# tvout_terminal.net
KiCad netlist of a schematic drawn in EAGLE
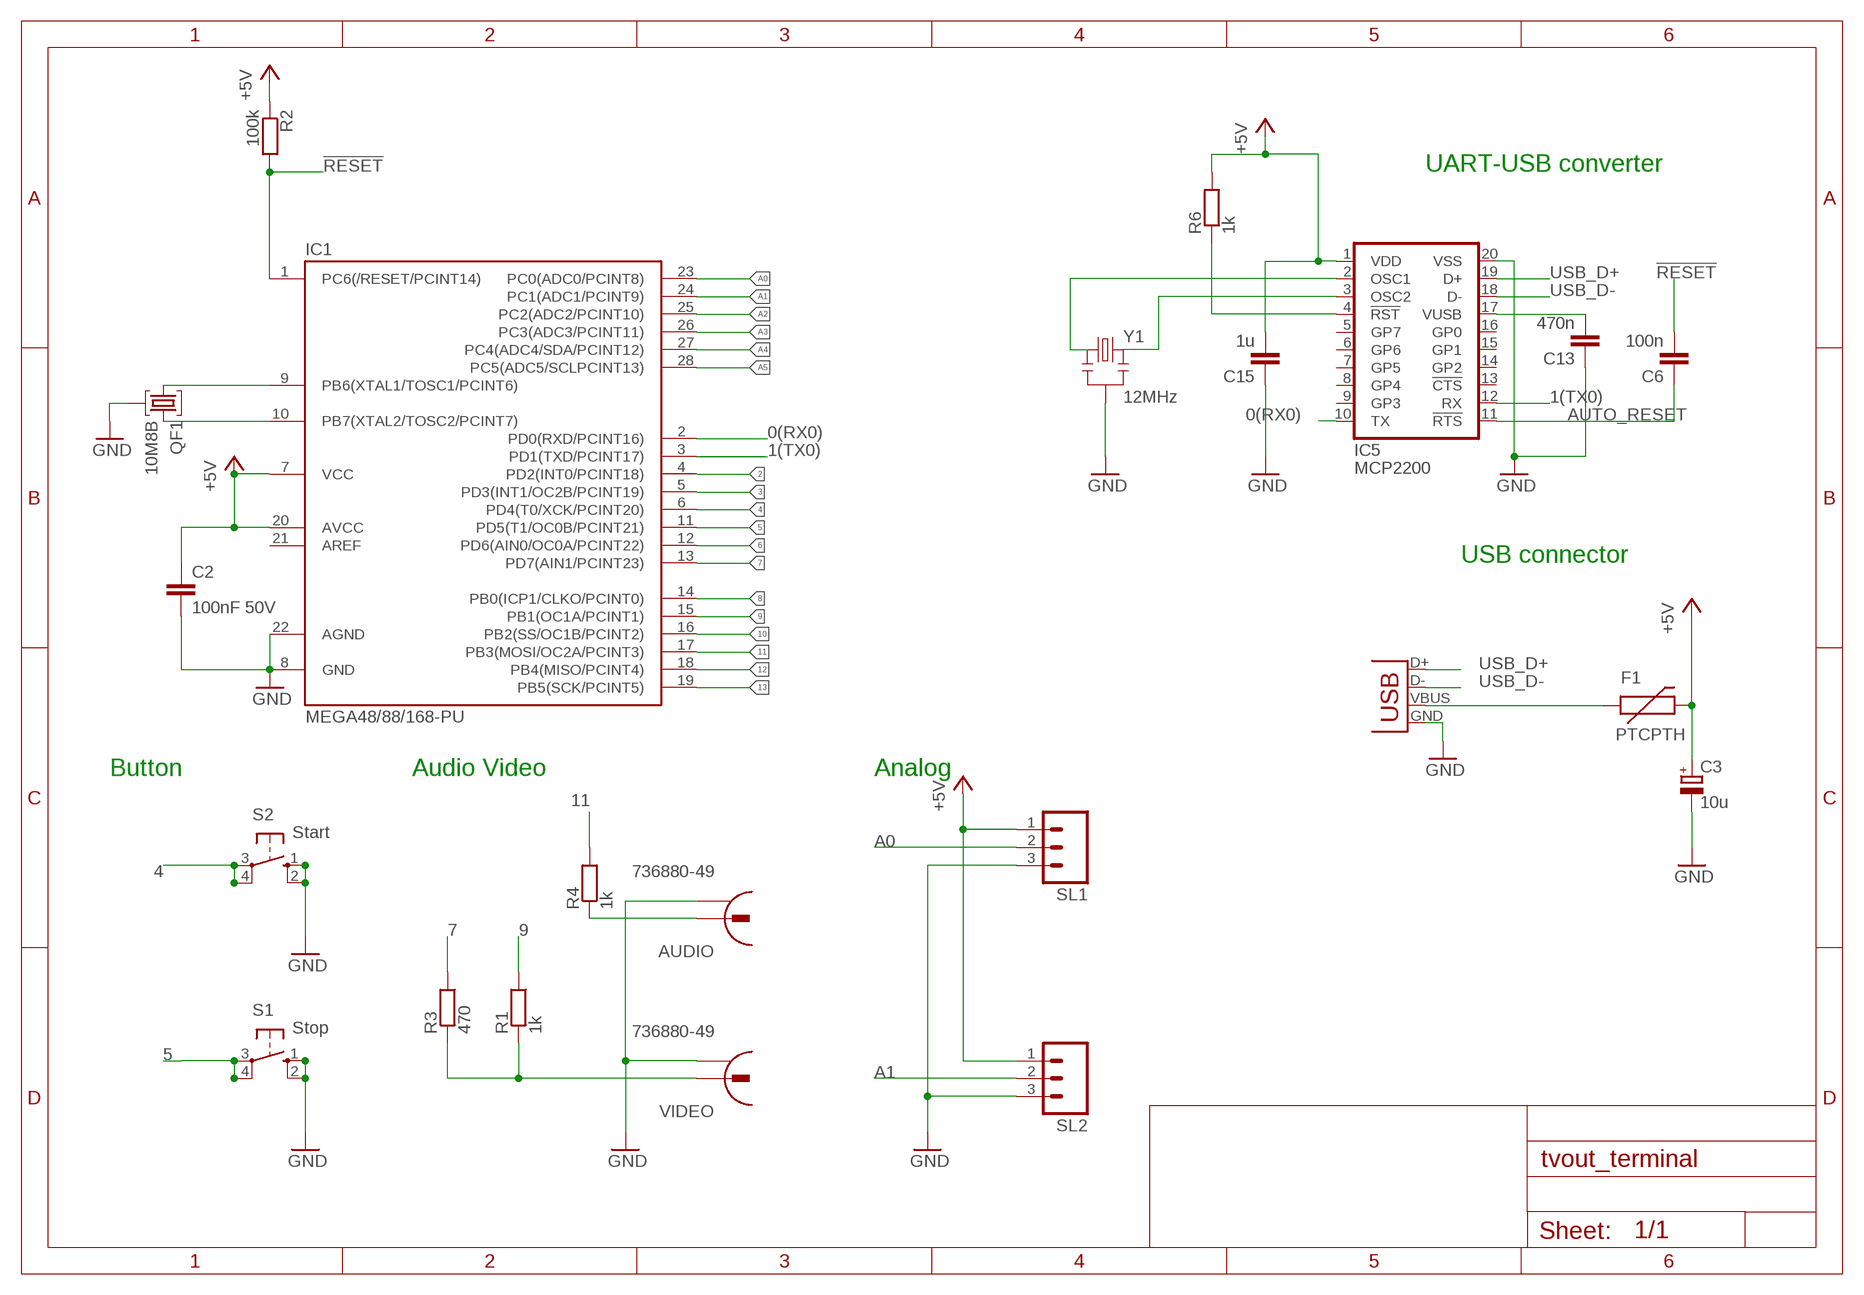
[diagram p0: schematic, sheet 1]

(export (version "E")
  (design (tool "Eeschema 10.0.6"))
  (components
    (comp (ref "AUDIO")
      (value "736880-49")
      (footprint "eagle-import:736880-49")
      (libsource (lib "eagle-import") (part "736880-49"))
    )
    (comp (ref "C2")
      (value "100nF 50V")
      (footprint "eagle-import:C025-025X050")
      (libsource (lib "eagle-import") (part "C-EU025-025X050"))
    )
    (comp (ref "C3")
      (value "10u")
      (footprint "eagle-import:E2,5-7")
      (libsource (lib "eagle-import") (part "CPOL-EUE2.5-7"))
    )
    (comp (ref "C6")
      (value "100n")
      (footprint "eagle-import:CAP-PTH-SMALL")
      (libsource (lib "eagle-import") (part "CAPPTH"))
    )
    (comp (ref "C13")
      (value "470n")
      (footprint "eagle-import:CAP-PTH-SMALL")
      (libsource (lib "eagle-import") (part "CAPPTH"))
    )
    (comp (ref "C15")
      (value "1u")
      (footprint "eagle-import:CAP-PTH-SMALL")
      (libsource (lib "eagle-import") (part "CAPPTH"))
    )
    (comp (ref "F1")
      (value "PTCPTH")
      (footprint "eagle-import:PTC")
      (libsource (lib "eagle-import") (part "PTCPTH"))
    )
    (comp (ref "IC1")
      (value "MEGA48/88/168-PU")
      (footprint "eagle-import:DIL28-3")
      (libsource (lib "eagle-import") (part "MEGA48/88/168-PU"))
    )
    (comp (ref "IC5")
      (value "MCP2200")
      (footprint "eagle-import:SO20")
      (libsource (lib "eagle-import") (part "MCP2200"))
    )
    (comp (ref "QF1")
      (value "10M8B")
      (footprint "eagle-import:HC49U")
      (fields (field (name "OC_FARNELL") "1448129"))
      (libsource (lib "eagle-import") (part "10MB8"))
    )
    (comp (ref "R1")
      (value "1k")
      (footprint "eagle-import:RES-AXIAL-0.4")
      (libsource (lib "eagle-import") (part "RESISTOR"))
    )
    (comp (ref "R2")
      (value "100k")
      (footprint "eagle-import:RES-AXIAL-0.4")
      (libsource (lib "eagle-import") (part "RESISTOR"))
    )
    (comp (ref "R3")
      (value "470")
      (footprint "eagle-import:RES-AXIAL-0.4")
      (libsource (lib "eagle-import") (part "RESISTOR"))
    )
    (comp (ref "R4")
      (value "1k")
      (footprint "eagle-import:RES-AXIAL-0.4")
      (libsource (lib "eagle-import") (part "RESISTOR"))
    )
    (comp (ref "R6")
      (value "1k")
      (footprint "eagle-import:RES-AXIAL-0.4")
      (libsource (lib "eagle-import") (part "RESISTOR"))
    )
    (comp (ref "S1")
      (value "Stop")
      (footprint "eagle-import:B3F-10XX")
      (fields (field (name "MPN") "B3F-1000"))
      (libsource (lib "eagle-import") (part "10-XX"))
    )
    (comp (ref "S2")
      (value "Start")
      (footprint "eagle-import:B3F-10XX")
      (fields (field (name "MPN") "B3F-1000"))
      (libsource (lib "eagle-import") (part "10-XX"))
    )
    (comp (ref "SL1")
      (value "M03")
      (footprint "eagle-import:03P")
      (libsource (lib "eagle-import") (part "M03"))
    )
    (comp (ref "SL2")
      (value "M03")
      (footprint "eagle-import:03P")
      (libsource (lib "eagle-import") (part "M03"))
    )
    (comp (ref "VIDEO")
      (value "736880-49")
      (footprint "eagle-import:736880-49")
      (libsource (lib "eagle-import") (part "736880-49"))
    )
    (comp (ref "X3")
      (value "USB")
      (footprint "eagle-import:USB-B-PTH")
      (libsource (lib "eagle-import") (part "USBPTH"))
    )
    (comp (ref "Y1")
      (value "12MHz")
      (footprint "eagle-import:HC49U-V-RESONATOR")
      (libsource (lib "eagle-import") (part "CRYSTAL-RESONATOR"))
    )
  )
  (nets
    (net (code "1") (name "+5V") (class "Default")
      (node (ref "C15") (pin "2") (pinfunction "2_2") (pintype "passive"))
      (node (ref "C2") (pin "1") (pinfunction "1_1") (pintype "passive"))
      (node (ref "C3") (pin "+") (pinfunction "+_+") (pintype "passive"))
      (node (ref "F1") (pin "P$2") (pinfunction "2_P$2") (pintype "bidirectional"))
      (node (ref "IC1") (pin "20") (pinfunction "AVCC_20") (pintype "passive"))
      (node (ref "IC1") (pin "7") (pinfunction "VCC_7") (pintype "power_in"))
      (node (ref "IC5") (pin "1") (pinfunction "VDD_1") (pintype "power_in"))
      (node (ref "R2") (pin "P$1") (pinfunction "1_P$1") (pintype "passive"))
      (node (ref "R6") (pin "P$2") (pinfunction "2_P$2") (pintype "passive"))
      (node (ref "SL1") (pin "1") (pinfunction "1_1") (pintype "passive"))
      (node (ref "SL2") (pin "1") (pinfunction "1_1") (pintype "passive"))
    )
    (net (code "2") (name "/0(RX0)") (class "Default")
      (node (ref "IC1") (pin "2") (pinfunction "PD0(RXD/PCINT16)_2") (pintype "bidirectional"))
      (node (ref "IC5") (pin "10") (pinfunction "TX_10") (pintype "bidirectional"))
    )
    (net (code "3") (name "/1(TX0)") (class "Default")
      (node (ref "IC1") (pin "3") (pinfunction "PD1(TXD/PCINT17)_3") (pintype "bidirectional"))
      (node (ref "IC5") (pin "12") (pinfunction "RX_12") (pintype "bidirectional"))
    )
    (net (code "4") (name "/AUTO_RESET") (class "Default")
      (node (ref "C6") (pin "1") (pinfunction "1_1") (pintype "passive"))
      (node (ref "IC5") (pin "11") (pinfunction "~{RTS}_11") (pintype "bidirectional"))
    )
    (net (code "5") (name "/USB_D+") (class "Default")
      (node (ref "IC5") (pin "19") (pinfunction "D+_19") (pintype "bidirectional"))
      (node (ref "X3") (pin "D+") (pinfunction "D+_D+") (pintype "bidirectional"))
    )
    (net (code "6") (name "/USB_D-") (class "Default")
      (node (ref "IC5") (pin "18") (pinfunction "D-_18") (pintype "bidirectional"))
      (node (ref "X3") (pin "D-") (pinfunction "D-_D-") (pintype "bidirectional"))
    )
    (net (code "7") (name "/~{RESET}") (class "Default")
      (node (ref "C6") (pin "2") (pinfunction "2_2") (pintype "passive"))
      (node (ref "IC1") (pin "1") (pinfunction "PC6(/RESET/PCINT14)_1") (pintype "bidirectional"))
      (node (ref "R2") (pin "P$2") (pinfunction "2_P$2") (pintype "passive"))
    )
    (net (code "8") (name "2") (class "Default")
      (node (ref "IC1") (pin "4") (pinfunction "PD2(INT0/PCINT18)_4") (pintype "bidirectional"))
    )
    (net (code "9") (name "3") (class "Default")
      (node (ref "IC1") (pin "5") (pinfunction "PD3(INT1/OC2B/PCINT19)_5") (pintype "bidirectional"))
    )
    (net (code "10") (name "4") (class "Default")
      (node (ref "IC1") (pin "6") (pinfunction "PD4(T0/XCK/PCINT20)_6") (pintype "bidirectional"))
      (node (ref "S2") (pin "3") (pinfunction "P_3") (pintype "passive"))
      (node (ref "S2") (pin "4") (pinfunction "P1_4") (pintype "passive"))
    )
    (net (code "11") (name "5") (class "Default")
      (node (ref "IC1") (pin "11") (pinfunction "PD5(T1/OC0B/PCINT21)_11") (pintype "bidirectional"))
      (node (ref "S1") (pin "3") (pinfunction "P_3") (pintype "passive"))
      (node (ref "S1") (pin "4") (pinfunction "P1_4") (pintype "passive"))
    )
    (net (code "12") (name "6") (class "Default")
      (node (ref "IC1") (pin "12") (pinfunction "PD6(AIN0/OC0A/PCINT22)_12") (pintype "bidirectional"))
    )
    (net (code "13") (name "7") (class "Default")
      (node (ref "IC1") (pin "13") (pinfunction "PD7(AIN1/PCINT23)_13") (pintype "bidirectional"))
      (node (ref "R3") (pin "P$2") (pinfunction "2_P$2") (pintype "passive"))
    )
    (net (code "14") (name "8") (class "Default")
      (node (ref "IC1") (pin "14") (pinfunction "PB0(ICP1/CLKO/PCINT0)_14") (pintype "bidirectional"))
    )
    (net (code "15") (name "9") (class "Default")
      (node (ref "IC1") (pin "15") (pinfunction "PB1(OC1A/PCINT1)_15") (pintype "bidirectional"))
      (node (ref "R1") (pin "P$2") (pinfunction "2_P$2") (pintype "passive"))
    )
    (net (code "16") (name "10") (class "Default")
      (node (ref "IC1") (pin "16") (pinfunction "PB2(SS/OC1B/PCINT2)_16") (pintype "bidirectional"))
    )
    (net (code "17") (name "11") (class "Default")
      (node (ref "IC1") (pin "17") (pinfunction "PB3(MOSI/OC2A/PCINT3)_17") (pintype "bidirectional"))
      (node (ref "R4") (pin "P$2") (pinfunction "2_P$2") (pintype "passive"))
    )
    (net (code "18") (name "12") (class "Default")
      (node (ref "IC1") (pin "18") (pinfunction "PB4(MISO/PCINT4)_18") (pintype "bidirectional"))
    )
    (net (code "19") (name "13") (class "Default")
      (node (ref "IC1") (pin "19") (pinfunction "PB5(SCK/PCINT5)_19") (pintype "bidirectional"))
    )
    (net (code "20") (name "A0") (class "Default")
      (node (ref "IC1") (pin "23") (pinfunction "PC0(ADC0/PCINT8)_23") (pintype "bidirectional"))
      (node (ref "SL1") (pin "2") (pinfunction "2_2") (pintype "passive"))
    )
    (net (code "21") (name "A1") (class "Default")
      (node (ref "IC1") (pin "24") (pinfunction "PC1(ADC1/PCINT9)_24") (pintype "bidirectional"))
      (node (ref "SL2") (pin "2") (pinfunction "2_2") (pintype "passive"))
    )
    (net (code "22") (name "A2") (class "Default")
      (node (ref "IC1") (pin "25") (pinfunction "PC2(ADC2/PCINT10)_25") (pintype "bidirectional"))
    )
    (net (code "23") (name "A3") (class "Default")
      (node (ref "IC1") (pin "26") (pinfunction "PC3(ADC3/PCINT11)_26") (pintype "bidirectional"))
    )
    (net (code "24") (name "A4") (class "Default")
      (node (ref "IC1") (pin "27") (pinfunction "PC4(ADC4/SDA/PCINT12)_27") (pintype "bidirectional"))
    )
    (net (code "25") (name "A5") (class "Default")
      (node (ref "IC1") (pin "28") (pinfunction "PC5(ADC5/SCLPCINT13)_28") (pintype "bidirectional"))
    )
    (net (code "26") (name "GND") (class "Default")
      (node (ref "AUDIO") (pin "2") (pinfunction "2_2") (pintype "passive"))
      (node (ref "C13") (pin "1") (pinfunction "1_1") (pintype "passive"))
      (node (ref "C15") (pin "1") (pinfunction "1_1") (pintype "passive"))
      (node (ref "C2") (pin "2") (pinfunction "2_2") (pintype "passive"))
      (node (ref "C3") (pin "-") (pinfunction "-_-") (pintype "passive"))
      (node (ref "IC1") (pin "22") (pinfunction "AGND_22") (pintype "power_in"))
      (node (ref "IC1") (pin "8") (pinfunction "GND_8") (pintype "power_in"))
      (node (ref "IC5") (pin "20") (pinfunction "VSS_20") (pintype "power_in"))
      (node (ref "QF1") (pin "2") (pinfunction "2_2") (pintype "passive"))
      (node (ref "S1") (pin "1") (pinfunction "S_1") (pintype "passive"))
      (node (ref "S1") (pin "2") (pinfunction "S1_2") (pintype "passive"))
      (node (ref "S2") (pin "1") (pinfunction "S_1") (pintype "passive"))
      (node (ref "S2") (pin "2") (pinfunction "S1_2") (pintype "passive"))
      (node (ref "SL1") (pin "3") (pinfunction "3_3") (pintype "passive"))
      (node (ref "SL2") (pin "3") (pinfunction "3_3") (pintype "passive"))
      (node (ref "VIDEO") (pin "2") (pinfunction "2_2") (pintype "passive"))
      (node (ref "X3") (pin "GND") (pinfunction "GND_GND") (pintype "bidirectional"))
      (node (ref "Y1") (pin "GND") (pinfunction "2_GND") (pintype "passive"))
    )
    (net (code "27") (name "Net-(F1-1)") (class "Default")
      (node (ref "F1") (pin "P$1") (pinfunction "1_P$1") (pintype "bidirectional"))
      (node (ref "X3") (pin "VBUS") (pinfunction "VBUS_VBUS") (pintype "bidirectional"))
    )
    (net (code "28") (name "Net-(IC1-PB6(XTAL1{slash}TOSC1{slash}PCINT6))") (class "Default")
      (node (ref "IC1") (pin "9") (pinfunction "PB6(XTAL1/TOSC1/PCINT6)_9") (pintype "bidirectional"))
      (node (ref "QF1") (pin "1") (pinfunction "1_1") (pintype "passive"))
    )
    (net (code "29") (name "Net-(IC1-PB7(XTAL2{slash}TOSC2{slash}PCINT7))") (class "Default")
      (node (ref "IC1") (pin "10") (pinfunction "PB7(XTAL2/TOSC2/PCINT7)_10") (pintype "bidirectional"))
      (node (ref "QF1") (pin "3") (pinfunction "3_3") (pintype "passive"))
    )
    (net (code "30") (name "Net-(IC5-OSC1)") (class "Default")
      (node (ref "IC5") (pin "2") (pinfunction "OSC1_2") (pintype "bidirectional"))
      (node (ref "Y1") (pin "1") (pinfunction "1_1") (pintype "passive"))
    )
    (net (code "31") (name "Net-(IC5-OSC2)") (class "Default")
      (node (ref "IC5") (pin "3") (pinfunction "OSC2_3") (pintype "bidirectional"))
      (node (ref "Y1") (pin "2") (pinfunction "3_2") (pintype "passive"))
    )
    (net (code "32") (name "Net-(IC5-VUSB)") (class "Default")
      (node (ref "C13") (pin "2") (pinfunction "2_2") (pintype "passive"))
      (node (ref "IC5") (pin "17") (pinfunction "VUSB_17") (pintype "bidirectional"))
    )
    (net (code "33") (name "Net-(IC5-~{RST})") (class "Default")
      (node (ref "IC5") (pin "4") (pinfunction "~{RST}_4") (pintype "bidirectional"))
      (node (ref "R6") (pin "P$1") (pinfunction "1_P$1") (pintype "passive"))
    )
    (net (code "34") (name "Net-(R1-1)") (class "Default")
      (node (ref "R1") (pin "P$1") (pinfunction "1_P$1") (pintype "passive"))
      (node (ref "R3") (pin "P$1") (pinfunction "1_P$1") (pintype "passive"))
      (node (ref "VIDEO") (pin "1") (pinfunction "1_1") (pintype "passive"))
    )
    (net (code "35") (name "Net-(R4-1)") (class "Default")
      (node (ref "AUDIO") (pin "1") (pinfunction "1_1") (pintype "passive"))
      (node (ref "R4") (pin "P$1") (pinfunction "1_P$1") (pintype "passive"))
    )
    (net (code "36") (name "unconnected-(AUDIO-2-Pad2@2)") (class "Default")
      (node (ref "AUDIO") (pin "2@2") (pinfunction "2_2@2") (pintype "passive"))
    )
    (net (code "37") (name "unconnected-(IC1-AREF-Pad21)") (class "Default")
      (node (ref "IC1") (pin "21") (pinfunction "AREF_21") (pintype "passive"))
    )
    (net (code "38") (name "unconnected-(IC5-GP0-Pad16)") (class "Default")
      (node (ref "IC5") (pin "16") (pinfunction "GP0_16") (pintype "bidirectional"))
    )
    (net (code "39") (name "unconnected-(IC5-GP1-Pad15)") (class "Default")
      (node (ref "IC5") (pin "15") (pinfunction "GP1_15") (pintype "bidirectional"))
    )
    (net (code "40") (name "unconnected-(IC5-GP2-Pad14)") (class "Default")
      (node (ref "IC5") (pin "14") (pinfunction "GP2_14") (pintype "bidirectional"))
    )
    (net (code "41") (name "unconnected-(IC5-GP3-Pad9)") (class "Default")
      (node (ref "IC5") (pin "9") (pinfunction "GP3_9") (pintype "bidirectional"))
    )
    (net (code "42") (name "unconnected-(IC5-GP4-Pad8)") (class "Default")
      (node (ref "IC5") (pin "8") (pinfunction "GP4_8") (pintype "bidirectional"))
    )
    (net (code "43") (name "unconnected-(IC5-GP5-Pad7)") (class "Default")
      (node (ref "IC5") (pin "7") (pinfunction "GP5_7") (pintype "bidirectional"))
    )
    (net (code "44") (name "unconnected-(IC5-GP6-Pad6)") (class "Default")
      (node (ref "IC5") (pin "6") (pinfunction "GP6_6") (pintype "bidirectional"))
    )
    (net (code "45") (name "unconnected-(IC5-GP7-Pad5)") (class "Default")
      (node (ref "IC5") (pin "5") (pinfunction "GP7_5") (pintype "bidirectional"))
    )
    (net (code "46") (name "unconnected-(IC5-~{CTS}-Pad13)") (class "Default")
      (node (ref "IC5") (pin "13") (pinfunction "~{CTS}_13") (pintype "bidirectional"))
    )
    (net (code "47") (name "unconnected-(VIDEO-2-Pad2@2)") (class "Default")
      (node (ref "VIDEO") (pin "2@2") (pinfunction "2_2@2") (pintype "passive"))
    )
  )
)
